# Input-Connectors.net
KiCad netlist of a schematic drawn in Altium Designer
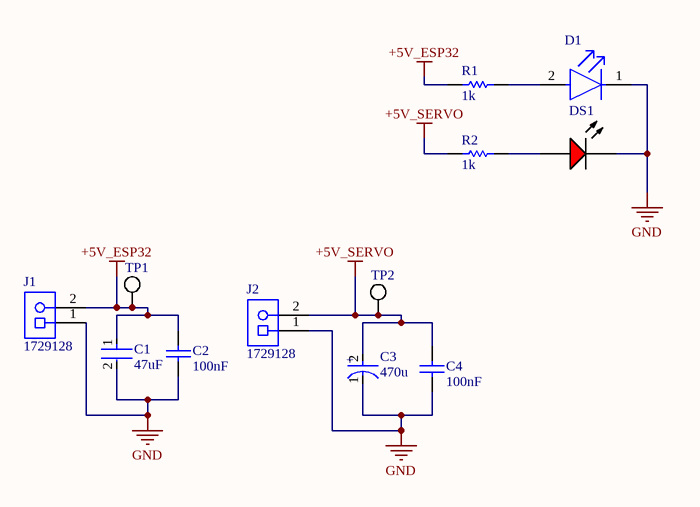
[diagram p0: Input-Connectors.SchDoc]

(export (version "E")
  (design (tool "Eeschema 10.0.6"))
  (components
    (comp (ref "C1")
      (value "47uF")
      (footprint "FP-CL32-IPC_C")
      (description "Cap Ceramic 47uF 16V X5R ±20% SMD 1210 +85°C Embossed T/R; CL32A476MOJNNWE")
      (libsource (lib "Altium Content Vault") (part "b4654b650e69147ec39a6b967a45e02"))
    )
    (comp (ref "C2")
      (value "100nF")
      (footprint "CAPC1206(3216)170_L")
      (description "CAP 100nF 50V ±10% 1206 (3216 Metric) Thickness 1.7mm SMD")
      (fields (field (name "TOLERANCE") "Â±10%"))
      (libsource (lib "Altium Content Vault") (part "CAP"))
    )
    (comp (ref "C3")
      (value "470u")
      (footprint "FP-RAD-TH-D_10_0_5-L_12_5-MFG")
      (description "Aluminum Electrolytic Capacitors (Radial Lead Type) 470uF ±20% 16V")
      (fields (field (name "TOLERANCE") "20%"))
      (libsource (lib "Altium Content Vault") (part "203bc49f2ac43e59fd269a8c329ed05"))
    )
    (comp (ref "C4")
      (value "100nF")
      (footprint "CAPC1206(3216)170_L")
      (description "CAP 100nF 50V ±10% 1206 (3216 Metric) Thickness 1.7mm SMD")
      (fields (field (name "TOLERANCE") "Â±10%"))
      (libsource (lib "Altium Content Vault") (part "CAP"))
    )
    (comp (ref "D1")
      (value "598-8270-107F")
      (footprint "FP-598-8270-107F-MFG")
      (description "SM LED 1206 ALINGAP G 7 REEL")
      (libsource (lib "Altium Content Vault") (part "8706943c75ba83719d021d2fdc84c58"))
    )
    (comp (ref "DS1")
      (value "SML-LX1206IC-TR")
      (footprint "LUMX-SML-LX1206IC_V")
      (description "LED Red, 65 mW, -40 to 85 degC, 2-Pin SMD, RoHS, Tape and Reel")
      (fields (field (name "MANUFACTURER") "Lumex"))
      (libsource (lib "Altium Content Vault") (part "LED-RED-AK-2"))
    )
    (comp (ref "J1")
      (value "1729128")
      (footprint "PHOE-1729128-2_V")
      (description "PCB Terminal Block, 13.5 A, 400 V, 2-Pin THD, RoHS, Bulk")
      (fields (field (name "MANUFACTURER") "Phoenix Contact"))
      (libsource (lib "Altium Content Vault") (part "CN-2P-F-R2"))
    )
    (comp (ref "J2")
      (value "1729128")
      (footprint "PHOE-1729128-2_V")
      (description "PCB Terminal Block, 13.5 A, 400 V, 2-Pin THD, RoHS, Bulk")
      (fields (field (name "MANUFACTURER") "Phoenix Contact"))
      (libsource (lib "Altium Content Vault") (part "CN-2P-F-R2"))
    )
    (comp (ref "R1")
      (value "1k")
      (footprint "RESC3216X60X45ML10T20")
      (fields (field (name "MANUFACTURER") "Vishay Dale") (field (name "PART NUMBER") "CRCW12061K00JNTA"))
      (libsource (lib "Altium Content Vault") (part "RES"))
    )
    (comp (ref "R2")
      (value "1k")
      (footprint "RESC3216X60X45ML10T20")
      (fields (field (name "MANUFACTURER") "Vishay Dale") (field (name "PART NUMBER") "CRCW12061K00JNTA"))
      (libsource (lib "Altium Content Vault") (part "RES"))
    )
    (comp (ref "TP1")
      (value "Test Point")
      (footprint "Test Point")
      (libsource (lib "University of California, Riverside") (part "Test Point"))
    )
    (comp (ref "TP2")
      (value "Test Point")
      (footprint "Test Point")
      (libsource (lib "University of California, Riverside") (part "Test Point"))
    )
  )
  (nets
    (net (code "1") (name "+5V_ESP32") (class "Default")
      (node (ref "C1") (pin "1") (pinfunction "1_1") (pintype "passive"))
      (node (ref "C2") (pin "2") (pinfunction "2_2") (pintype "passive"))
      (node (ref "J1") (pin "2") (pinfunction "2_2") (pintype "passive"))
      (node (ref "R1") (pin "1") (pinfunction "1_1") (pintype "passive"))
      (node (ref "TP1") (pin "1") (pinfunction "1_1") (pintype "passive"))
    )
    (net (code "2") (name "+5V_SERVO") (class "Default")
      (node (ref "C3") (pin "2") (pinfunction "A_2") (pintype "passive"))
      (node (ref "C4") (pin "2") (pinfunction "2_2") (pintype "passive"))
      (node (ref "J2") (pin "2") (pinfunction "2_2") (pintype "passive"))
      (node (ref "R2") (pin "1") (pinfunction "1_1") (pintype "passive"))
      (node (ref "TP2") (pin "1") (pinfunction "1_1") (pintype "passive"))
    )
    (net (code "3") (name "GND") (class "Default")
      (node (ref "C1") (pin "2") (pinfunction "2_2") (pintype "passive"))
      (node (ref "C2") (pin "1") (pinfunction "1_1") (pintype "passive"))
      (node (ref "C3") (pin "1") (pinfunction "C_1") (pintype "passive"))
      (node (ref "C4") (pin "1") (pinfunction "1_1") (pintype "passive"))
      (node (ref "D1") (pin "1") (pinfunction "C_1") (pintype "passive"))
      (node (ref "DS1") (pin "2") (pinfunction "K_2") (pintype "passive"))
      (node (ref "J1") (pin "1") (pinfunction "1_1") (pintype "passive"))
      (node (ref "J2") (pin "1") (pinfunction "1_1") (pintype "passive"))
    )
    (net (code "4") (name "Net-(D1-A)") (class "Default")
      (node (ref "D1") (pin "2") (pinfunction "A_2") (pintype "passive"))
      (node (ref "R1") (pin "2") (pinfunction "2_2") (pintype "passive"))
    )
    (net (code "5") (name "Net-(DS1-A)") (class "Default")
      (node (ref "DS1") (pin "1") (pinfunction "A_1") (pintype "passive"))
      (node (ref "R2") (pin "2") (pinfunction "2_2") (pintype "passive"))
    )
  )
)
